# 08_FPGA.net
KiCad netlist of a schematic drawn in Altium Designer
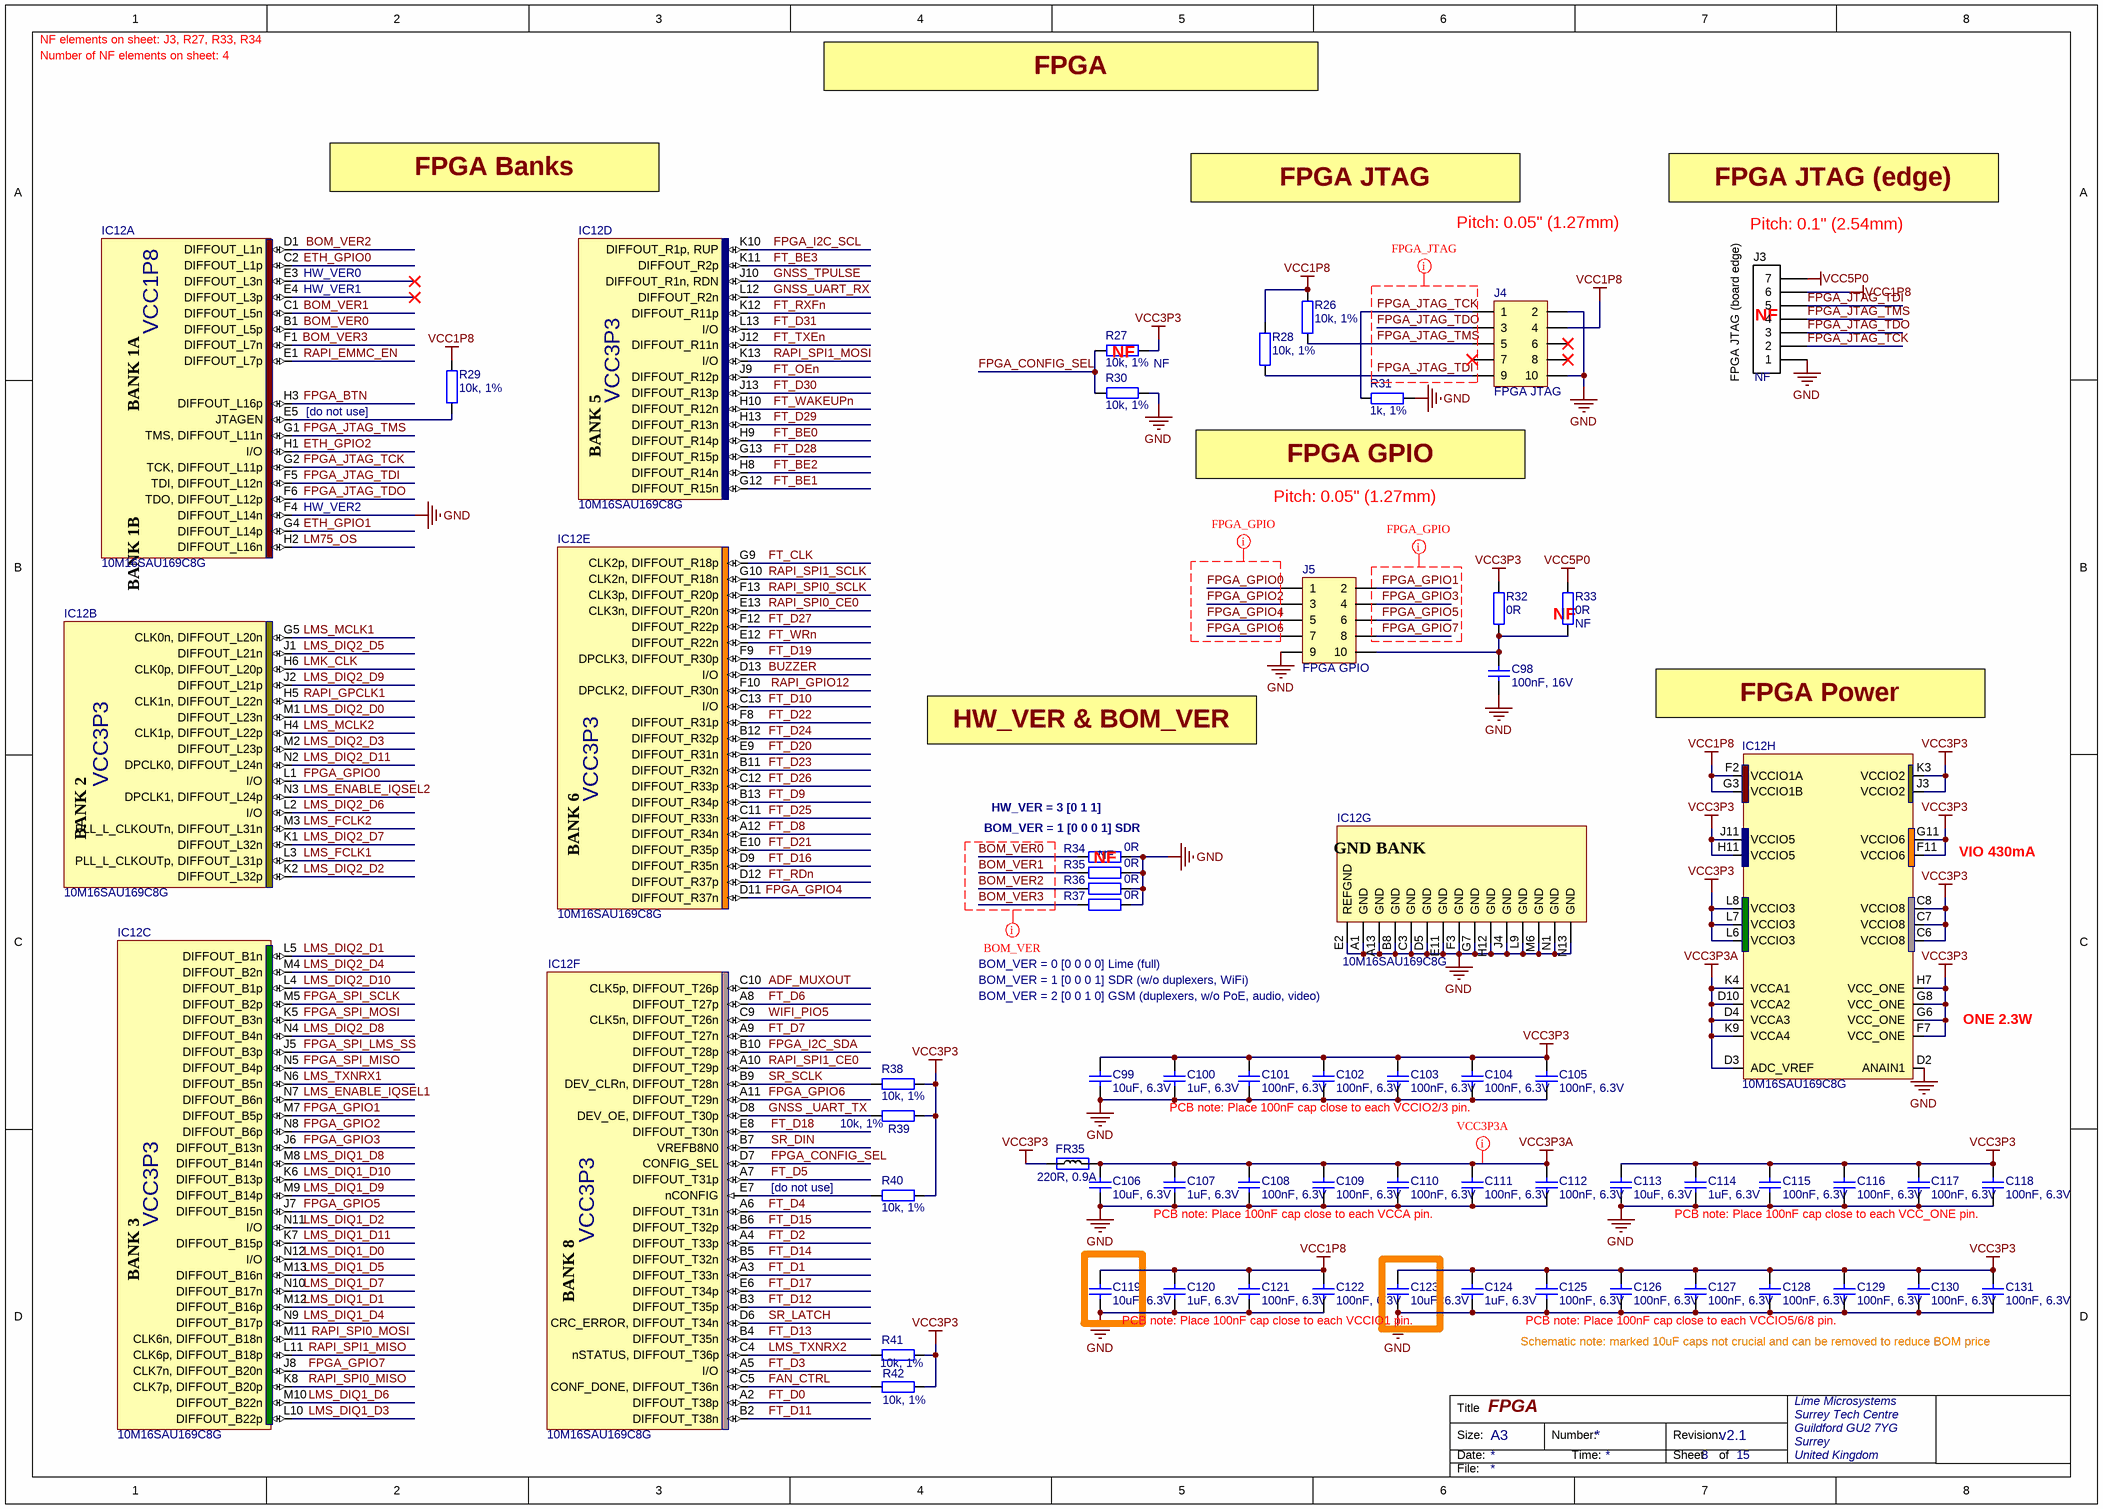
[diagram p0: 08_FPGA.SchDoc]

(export (version "E")
  (design (tool "Eeschema 10.0.6"))
  (components
    (comp (ref "C98")
      (value "100nF, 16V")
      (footprint "CAP0402")
      (fields
        (field (name "MANUFACTURER") "Murata Electronics")
        (field (name "TOLERANCE") "10 %")
        (field (name "MANUFACTURER PART NUMBER") "GRM155R71C104KA88D")
      )
      (libsource (lib "LimeMicroAltiumLib_schLib") (part "Cap_0402"))
    )
    (comp (ref "C99")
      (value "10uF, 6.3V")
      (footprint "CAP0603")
      (fields (field (name "TOLERANCE") "±20%") (field (name "MANUFACTURER") "Yageo"))
      (libsource (lib "LimeFPGAboard_schLib") (part "Cap_0603"))
    )
    (comp (ref "C100")
      (value "1uF, 6.3V")
      (footprint "CAP0201")
      (fields (field (name "TOLERANCE") "±20%") (field (name "MANUFACTURER") "TDK Corporation"))
      (libsource (lib "LimeMicroAltiumLib_schLib") (part "Cap_0402"))
    )
    (comp (ref "C101")
      (value "100nF, 6.3V")
      (footprint "CAP0201")
      (fields (field (name "MANUFACTURER") "Murata") (field (name "TOLERANCE") "10 %"))
      (libsource (lib "LimeMicroAltiumLib_schLib") (part "Cap_0402"))
    )
    (comp (ref "C102")
      (value "100nF, 6.3V")
      (footprint "CAP0201")
      (fields (field (name "MANUFACTURER") "Murata") (field (name "TOLERANCE") "10 %"))
      (libsource (lib "LimeMicroAltiumLib_schLib") (part "Cap_0402"))
    )
    (comp (ref "C103")
      (value "100nF, 6.3V")
      (footprint "CAP0201")
      (fields (field (name "MANUFACTURER") "Murata") (field (name "TOLERANCE") "10 %"))
      (libsource (lib "LimeMicroAltiumLib_schLib") (part "Cap_0402"))
    )
    (comp (ref "C104")
      (value "100nF, 6.3V")
      (footprint "CAP0201")
      (fields (field (name "MANUFACTURER") "Murata") (field (name "TOLERANCE") "10 %"))
      (libsource (lib "LimeMicroAltiumLib_schLib") (part "Cap_0402"))
    )
    (comp (ref "C105")
      (value "100nF, 6.3V")
      (footprint "CAP0201")
      (fields (field (name "MANUFACTURER") "Murata") (field (name "TOLERANCE") "10 %"))
      (libsource (lib "LimeMicroAltiumLib_schLib") (part "Cap_0402"))
    )
    (comp (ref "C106")
      (value "10uF, 6.3V")
      (footprint "CAP0603")
      (fields (field (name "TOLERANCE") "±20%") (field (name "MANUFACTURER") "Yageo"))
      (libsource (lib "LimeFPGAboard_schLib") (part "Cap_0603"))
    )
    (comp (ref "C107")
      (value "1uF, 6.3V")
      (footprint "CAP0201")
      (fields (field (name "TOLERANCE") "±20%") (field (name "MANUFACTURER") "TDK Corporation"))
      (libsource (lib "LimeMicroAltiumLib_schLib") (part "Cap_0402"))
    )
    (comp (ref "C108")
      (value "100nF, 6.3V")
      (footprint "CAP0201")
      (fields (field (name "MANUFACTURER") "Murata") (field (name "TOLERANCE") "10 %"))
      (libsource (lib "LimeMicroAltiumLib_schLib") (part "Cap_0402"))
    )
    (comp (ref "C109")
      (value "100nF, 6.3V")
      (footprint "CAP0201")
      (fields (field (name "MANUFACTURER") "Murata") (field (name "TOLERANCE") "10 %"))
      (libsource (lib "LimeMicroAltiumLib_schLib") (part "Cap_0402"))
    )
    (comp (ref "C110")
      (value "100nF, 6.3V")
      (footprint "CAP0201")
      (fields (field (name "MANUFACTURER") "Murata") (field (name "TOLERANCE") "10 %"))
      (libsource (lib "LimeMicroAltiumLib_schLib") (part "Cap_0402"))
    )
    (comp (ref "C111")
      (value "100nF, 6.3V")
      (footprint "CAP0201")
      (fields (field (name "MANUFACTURER") "Murata") (field (name "TOLERANCE") "10 %"))
      (libsource (lib "LimeMicroAltiumLib_schLib") (part "Cap_0402"))
    )
    (comp (ref "C112")
      (value "100nF, 6.3V")
      (footprint "CAP0201")
      (fields (field (name "MANUFACTURER") "Murata") (field (name "TOLERANCE") "10 %"))
      (libsource (lib "LimeMicroAltiumLib_schLib") (part "Cap_0402"))
    )
    (comp (ref "C113")
      (value "10uF, 6.3V")
      (footprint "CAP0603")
      (fields (field (name "TOLERANCE") "±20%") (field (name "MANUFACTURER") "Yageo"))
      (libsource (lib "LimeFPGAboard_schLib") (part "Cap_0603"))
    )
    (comp (ref "C114")
      (value "1uF, 6.3V")
      (footprint "CAP0201")
      (fields (field (name "TOLERANCE") "±20%") (field (name "MANUFACTURER") "TDK Corporation"))
      (libsource (lib "LimeMicroAltiumLib_schLib") (part "Cap_0402"))
    )
    (comp (ref "C115")
      (value "100nF, 6.3V")
      (footprint "CAP0201")
      (fields (field (name "MANUFACTURER") "Murata") (field (name "TOLERANCE") "10 %"))
      (libsource (lib "LimeMicroAltiumLib_schLib") (part "Cap_0402"))
    )
    (comp (ref "C116")
      (value "100nF, 6.3V")
      (footprint "CAP0201")
      (fields (field (name "MANUFACTURER") "Murata") (field (name "TOLERANCE") "10 %"))
      (libsource (lib "LimeMicroAltiumLib_schLib") (part "Cap_0402"))
    )
    (comp (ref "C117")
      (value "100nF, 6.3V")
      (footprint "CAP0201")
      (fields (field (name "MANUFACTURER") "Murata") (field (name "TOLERANCE") "10 %"))
      (libsource (lib "LimeMicroAltiumLib_schLib") (part "Cap_0402"))
    )
    (comp (ref "C118")
      (value "100nF, 6.3V")
      (footprint "CAP0201")
      (fields (field (name "MANUFACTURER") "Murata") (field (name "TOLERANCE") "10 %"))
      (libsource (lib "LimeMicroAltiumLib_schLib") (part "Cap_0402"))
    )
    (comp (ref "C119")
      (value "10uF, 6.3V")
      (footprint "CAP0603")
      (fields (field (name "TOLERANCE") "±20%") (field (name "MANUFACTURER") "Yageo"))
      (libsource (lib "LimeFPGAboard_schLib") (part "Cap_0603"))
    )
    (comp (ref "C120")
      (value "1uF, 6.3V")
      (footprint "CAP0201")
      (fields (field (name "TOLERANCE") "±20%") (field (name "MANUFACTURER") "TDK Corporation"))
      (libsource (lib "LimeMicroAltiumLib_schLib") (part "Cap_0402"))
    )
    (comp (ref "C121")
      (value "100nF, 6.3V")
      (footprint "CAP0201")
      (fields (field (name "MANUFACTURER") "Murata") (field (name "TOLERANCE") "10 %"))
      (libsource (lib "LimeMicroAltiumLib_schLib") (part "Cap_0402"))
    )
    (comp (ref "C122")
      (value "100nF, 6.3V")
      (footprint "CAP0201")
      (fields (field (name "MANUFACTURER") "Murata") (field (name "TOLERANCE") "10 %"))
      (libsource (lib "LimeMicroAltiumLib_schLib") (part "Cap_0402"))
    )
    (comp (ref "C123")
      (value "10uF, 6.3V")
      (footprint "CAP0603")
      (fields (field (name "TOLERANCE") "±20%") (field (name "MANUFACTURER") "Yageo"))
      (libsource (lib "LimeFPGAboard_schLib") (part "Cap_0603"))
    )
    (comp (ref "C124")
      (value "1uF, 6.3V")
      (footprint "CAP0201")
      (fields (field (name "TOLERANCE") "±20%") (field (name "MANUFACTURER") "TDK Corporation"))
      (libsource (lib "LimeMicroAltiumLib_schLib") (part "Cap_0402"))
    )
    (comp (ref "C125")
      (value "100nF, 6.3V")
      (footprint "CAP0201")
      (fields (field (name "MANUFACTURER") "Murata") (field (name "TOLERANCE") "10 %"))
      (libsource (lib "LimeMicroAltiumLib_schLib") (part "Cap_0402"))
    )
    (comp (ref "C126")
      (value "100nF, 6.3V")
      (footprint "CAP0201")
      (fields (field (name "MANUFACTURER") "Murata") (field (name "TOLERANCE") "10 %"))
      (libsource (lib "LimeMicroAltiumLib_schLib") (part "Cap_0402"))
    )
    (comp (ref "C127")
      (value "100nF, 6.3V")
      (footprint "CAP0201")
      (fields (field (name "MANUFACTURER") "Murata") (field (name "TOLERANCE") "10 %"))
      (libsource (lib "LimeMicroAltiumLib_schLib") (part "Cap_0402"))
    )
    (comp (ref "C128")
      (value "100nF, 6.3V")
      (footprint "CAP0201")
      (fields (field (name "MANUFACTURER") "Murata") (field (name "TOLERANCE") "10 %"))
      (libsource (lib "LimeMicroAltiumLib_schLib") (part "Cap_0402"))
    )
    (comp (ref "C129")
      (value "100nF, 6.3V")
      (footprint "CAP0201")
      (fields (field (name "MANUFACTURER") "Murata") (field (name "TOLERANCE") "10 %"))
      (libsource (lib "LimeMicroAltiumLib_schLib") (part "Cap_0402"))
    )
    (comp (ref "C130")
      (value "100nF, 6.3V")
      (footprint "CAP0201")
      (fields (field (name "MANUFACTURER") "Murata") (field (name "TOLERANCE") "10 %"))
      (libsource (lib "LimeMicroAltiumLib_schLib") (part "Cap_0402"))
    )
    (comp (ref "C131")
      (value "100nF, 6.3V")
      (footprint "CAP0201")
      (fields (field (name "MANUFACTURER") "Murata") (field (name "TOLERANCE") "10 %"))
      (libsource (lib "LimeMicroAltiumLib_schLib") (part "Cap_0402"))
    )
    (comp (ref "FR35")
      (value "220R, 0.9A")
      (footprint "RES0402")
      (fields (field (name "MANUFACTURER") "TDK Corporation"))
      (libsource (lib "LimeFPGAboard_schLib") (part "Ferrite"))
    )
    (comp (ref "IC12")
      (value "10M16SAU169C8G")
      (footprint "10M16SAU169C8G")
      (fields (field (name "MANUFACTURER") "Altera"))
      (libsource (lib "LimeMicroAltiumLib_schLib") (part "10M16SAU169C8G"))
    )
    (comp (ref "J3")
      (value "FPGA JTAG (board edge)")
      (footprint "Header7x1_TH")
      (description "Header, 7-pin")
      (fields (field (name "MANUFACTURER") "Sullins Connector Solutions") (field (name "ASSEMBLY INFO") "NF"))
      (libsource (lib "LimeMicroAltiumLib_schLib") (part "Header7P"))
    )
    (comp (ref "J4")
      (value "FPGA JTAG")
      (footprint "SWD_10_pin")
      (description "Header, 5-Pin, Dual row")
      (fields (field (name "MANUFACTURER") "Harwin Inc"))
      (libsource (lib "LimeMicroAltiumLib_schLib") (part "Header 5X2_SWD"))
    )
    (comp (ref "J5")
      (value "FPGA GPIO")
      (footprint "SWD_10_pin")
      (description "Header, 5-Pin, Dual row")
      (fields (field (name "MANUFACTURER") "Harwin Inc"))
      (libsource (lib "LimeMicroAltiumLib_schLib") (part "Header 5X2_SWD"))
    )
    (comp (ref "R26")
      (value "10k, 1%")
      (footprint "RES0402")
      (fields (field (name "MANUFACTURER") "Yageo") (field (name "TOLERANCE") "±1%"))
      (libsource (lib "LimeMicroAltiumLib_schLib") (part "Res_0402"))
    )
    (comp (ref "R27")
      (value "10k, 1%")
      (footprint "RES0402")
      (fields
        (field (name "ASSEMBLY INFO") "NF")
        (field (name "MANUFACTURER") "Yageo")
        (field (name "TOLERANCE") "±1%")
      )
      (libsource (lib "LimeMicroAltiumLib_schLib") (part "Res_0402"))
    )
    (comp (ref "R28")
      (value "10k, 1%")
      (footprint "RES0402")
      (fields (field (name "MANUFACTURER") "Yageo") (field (name "TOLERANCE") "±1%"))
      (libsource (lib "LimeMicroAltiumLib_schLib") (part "Res_0402"))
    )
    (comp (ref "R29")
      (value "10k, 1%")
      (footprint "RES0402")
      (fields (field (name "MANUFACTURER") "Yageo") (field (name "TOLERANCE") "±1%"))
      (libsource (lib "LimeMicroAltiumLib_schLib") (part "Res_0402"))
    )
    (comp (ref "R30")
      (value "10k, 1%")
      (footprint "RES0402")
      (fields (field (name "MANUFACTURER") "Yageo") (field (name "TOLERANCE") "±1%"))
      (libsource (lib "LimeMicroAltiumLib_schLib") (part "Res_0402"))
    )
    (comp (ref "R31")
      (value "1k, 1%")
      (footprint "RES0402")
      (fields (field (name "MANUFACTURER") "Stackpole Electronics Inc") (field (name "TOLERANCE") "±1%"))
      (libsource (lib "LimeMicroAltiumLib_schLib") (part "Res_0402"))
    )
    (comp (ref "R32")
      (value "0R")
      (footprint "RES0402")
      (fields (field (name "MANUFACTURER") "Yageo") (field (name "TOLERANCE") "Jumper"))
      (libsource (lib "LimeFPGAboard_schLib") (part "Res_0402"))
    )
    (comp (ref "R33")
      (value "0R")
      (footprint "RES0402")
      (fields
        (field (name "MANUFACTURER") "Yageo")
        (field (name "ASSEMBLY INFO") "NF")
        (field (name "TOLERANCE") "Jumper")
      )
      (libsource (lib "LimeFPGAboard_schLib") (part "Res_0402"))
    )
    (comp (ref "R34")
      (value "0R")
      (footprint "RES0402")
      (fields
        (field (name "MANUFACTURER") "Yageo")
        (field (name "ASSEMBLY INFO") "NF")
        (field (name "TOLERANCE") "Jumper")
      )
      (libsource (lib "LimeFPGAboard_schLib") (part "Res_0402"))
    )
    (comp (ref "R35")
      (value "0R")
      (footprint "RES0402")
      (fields (field (name "MANUFACTURER") "Yageo") (field (name "TOLERANCE") "Jumper"))
      (libsource (lib "LimeFPGAboard_schLib") (part "Res_0402"))
    )
    (comp (ref "R36")
      (value "0R")
      (footprint "RES0402")
      (fields (field (name "MANUFACTURER") "Yageo") (field (name "TOLERANCE") "Jumper"))
      (libsource (lib "LimeFPGAboard_schLib") (part "Res_0402"))
    )
    (comp (ref "R37")
      (value "0R")
      (footprint "RES0402")
      (fields (field (name "MANUFACTURER") "Yageo") (field (name "TOLERANCE") "Jumper"))
      (libsource (lib "LimeFPGAboard_schLib") (part "Res_0402"))
    )
    (comp (ref "R38")
      (value "10k, 1%")
      (footprint "RES0402")
      (fields (field (name "MANUFACTURER") "Yageo") (field (name "TOLERANCE") "±1%"))
      (libsource (lib "LimeMicroAltiumLib_schLib") (part "Res_0402"))
    )
    (comp (ref "R39")
      (value "10k, 1%")
      (footprint "RES0402")
      (fields (field (name "MANUFACTURER") "Yageo") (field (name "TOLERANCE") "±1%"))
      (libsource (lib "LimeMicroAltiumLib_schLib") (part "Res_0402"))
    )
    (comp (ref "R40")
      (value "10k, 1%")
      (footprint "RES0402")
      (fields (field (name "MANUFACTURER") "Yageo") (field (name "TOLERANCE") "±1%"))
      (libsource (lib "LimeMicroAltiumLib_schLib") (part "Res_0402"))
    )
    (comp (ref "R41")
      (value "10k, 1%")
      (footprint "RES0402")
      (fields (field (name "MANUFACTURER") "Yageo") (field (name "TOLERANCE") "±1%"))
      (libsource (lib "LimeMicroAltiumLib_schLib") (part "Res_0402"))
    )
    (comp (ref "R42")
      (value "10k, 1%")
      (footprint "RES0402")
      (fields (field (name "MANUFACTURER") "Yageo") (field (name "TOLERANCE") "±1%"))
      (libsource (lib "LimeMicroAltiumLib_schLib") (part "Res_0402"))
    )
  )
  (nets
    (net (code "1") (name "/ADF_MUXOUT") (class "Default")
      (node (ref "IC12") (pin "C10") (pinfunction "CLK5p,_DIFFOUT_T26p_C10") (pintype "bidirectional"))
    )
    (net (code "2") (name "/BOM_VER0") (class "Default")
      (node (ref "IC12") (pin "B1") (pinfunction "DIFFOUT_L5p_B1") (pintype "bidirectional"))
      (node (ref "R34") (pin "2") (pinfunction "2_2") (pintype "passive"))
    )
    (net (code "3") (name "/BOM_VER1") (class "Default")
      (node (ref "IC12") (pin "C1") (pinfunction "DIFFOUT_L5n_C1") (pintype "bidirectional"))
      (node (ref "R35") (pin "2") (pinfunction "2_2") (pintype "passive"))
    )
    (net (code "4") (name "/BOM_VER2") (class "Default")
      (node (ref "IC12") (pin "D1") (pinfunction "DIFFOUT_L1n_D1") (pintype "bidirectional"))
      (node (ref "R36") (pin "2") (pinfunction "2_2") (pintype "passive"))
    )
    (net (code "5") (name "/BOM_VER3") (class "Default")
      (node (ref "IC12") (pin "F1") (pinfunction "DIFFOUT_L7n_F1") (pintype "bidirectional"))
      (node (ref "R37") (pin "2") (pinfunction "2_2") (pintype "passive"))
    )
    (net (code "6") (name "/BUZZER") (class "Default")
      (node (ref "IC12") (pin "D13") (pinfunction "I/O_D13") (pintype "bidirectional"))
    )
    (net (code "7") (name "/ETH_GPIO0") (class "Default")
      (node (ref "IC12") (pin "C2") (pinfunction "DIFFOUT_L1p_C2") (pintype "bidirectional"))
    )
    (net (code "8") (name "/ETH_GPIO1") (class "Default")
      (node (ref "IC12") (pin "G4") (pinfunction "DIFFOUT_L14p_G4") (pintype "bidirectional"))
    )
    (net (code "9") (name "/ETH_GPIO2") (class "Default")
      (node (ref "IC12") (pin "H1") (pinfunction "I/O_H1") (pintype "bidirectional"))
    )
    (net (code "10") (name "/FAN_CTRL") (class "Default")
      (node (ref "IC12") (pin "C5") (pinfunction "CONF_DONE,_DIFFOUT_T36n_C5") (pintype "bidirectional"))
      (node (ref "R42") (pin "2") (pinfunction "2_2") (pintype "passive"))
    )
    (net (code "11") (name "/FPGA_BTN") (class "Default")
      (node (ref "IC12") (pin "H3") (pinfunction "DIFFOUT_L16p_H3") (pintype "bidirectional"))
    )
    (net (code "12") (name "/FPGA_CONFIG_SEL") (class "Default")
      (node (ref "IC12") (pin "D7") (pinfunction "CONFIG_SEL_D7") (pintype "bidirectional"))
      (node (ref "R27") (pin "2") (pinfunction "2_2") (pintype "passive"))
      (node (ref "R30") (pin "2") (pinfunction "2_2") (pintype "passive"))
    )
    (net (code "13") (name "/FPGA_GPIO0") (class "Default")
      (node (ref "IC12") (pin "L1") (pinfunction "I/O_L1") (pintype "bidirectional"))
      (node (ref "J5") (pin "1") (pinfunction "1_1") (pintype "passive"))
    )
    (net (code "14") (name "/FPGA_GPIO1") (class "Default")
      (node (ref "IC12") (pin "M7") (pinfunction "DIFFOUT_B5p_M7") (pintype "bidirectional"))
      (node (ref "J5") (pin "2") (pinfunction "2_2") (pintype "passive"))
    )
    (net (code "15") (name "/FPGA_GPIO2") (class "Default")
      (node (ref "IC12") (pin "N8") (pinfunction "DIFFOUT_B6p_N8") (pintype "bidirectional"))
      (node (ref "J5") (pin "3") (pinfunction "3_3") (pintype "passive"))
    )
    (net (code "16") (name "/FPGA_GPIO3") (class "Default")
      (node (ref "IC12") (pin "J6") (pinfunction "DIFFOUT_B13n_J6") (pintype "bidirectional"))
      (node (ref "J5") (pin "4") (pinfunction "4_4") (pintype "passive"))
    )
    (net (code "17") (name "/FPGA_GPIO4") (class "Default")
      (node (ref "IC12") (pin "D11") (pinfunction "DIFFOUT_R37n_D11") (pintype "bidirectional"))
      (node (ref "J5") (pin "5") (pinfunction "5_5") (pintype "passive"))
    )
    (net (code "18") (name "/FPGA_GPIO5") (class "Default")
      (node (ref "IC12") (pin "J7") (pinfunction "DIFFOUT_B15n_J7") (pintype "bidirectional"))
      (node (ref "J5") (pin "6") (pinfunction "6_6") (pintype "passive"))
    )
    (net (code "19") (name "/FPGA_GPIO6") (class "Default")
      (node (ref "IC12") (pin "A11") (pinfunction "DIFFOUT_T29n_A11") (pintype "bidirectional"))
      (node (ref "J5") (pin "7") (pinfunction "7_7") (pintype "passive"))
    )
    (net (code "20") (name "/FPGA_GPIO7") (class "Default")
      (node (ref "IC12") (pin "J8") (pinfunction "CLK7n,_DIFFOUT_B20n_J8") (pintype "bidirectional"))
      (node (ref "J5") (pin "8") (pinfunction "8_8") (pintype "passive"))
    )
    (net (code "21") (name "/FPGA_I2C_SCL") (class "Default")
      (node (ref "IC12") (pin "K10") (pinfunction "DIFFOUT_R1p,_RUP_K10") (pintype "bidirectional"))
    )
    (net (code "22") (name "/FPGA_I2C_SDA") (class "Default")
      (node (ref "IC12") (pin "B10") (pinfunction "DIFFOUT_T28p_B10") (pintype "bidirectional"))
    )
    (net (code "23") (name "/FPGA_JTAG_TCK") (class "Default")
      (node (ref "IC12") (pin "G2") (pinfunction "TCK,_DIFFOUT_L11p_G2") (pintype "bidirectional"))
      (node (ref "J3") (pin "2") (pinfunction "2_2") (pintype "passive"))
      (node (ref "J4") (pin "1") (pinfunction "1_1") (pintype "passive"))
      (node (ref "R31") (pin "1") (pinfunction "1_1") (pintype "passive"))
    )
    (net (code "24") (name "/FPGA_JTAG_TDI") (class "Default")
      (node (ref "IC12") (pin "F5") (pinfunction "TDI,_DIFFOUT_L12n_F5") (pintype "bidirectional"))
      (node (ref "J3") (pin "5") (pinfunction "5_5") (pintype "passive"))
      (node (ref "J4") (pin "9") (pinfunction "9_9") (pintype "passive"))
      (node (ref "R28") (pin "1") (pinfunction "1_1") (pintype "passive"))
    )
    (net (code "25") (name "/FPGA_JTAG_TDO") (class "Default")
      (node (ref "IC12") (pin "F6") (pinfunction "TDO,_DIFFOUT_L12p_F6") (pintype "bidirectional"))
      (node (ref "J3") (pin "3") (pinfunction "3_3") (pintype "passive"))
      (node (ref "J4") (pin "3") (pinfunction "3_3") (pintype "passive"))
    )
    (net (code "26") (name "/FPGA_JTAG_TMS") (class "Default")
      (node (ref "IC12") (pin "G1") (pinfunction "TMS,_DIFFOUT_L11n_G1") (pintype "bidirectional"))
      (node (ref "J3") (pin "4") (pinfunction "4_4") (pintype "passive"))
      (node (ref "J4") (pin "5") (pinfunction "5_5") (pintype "passive"))
      (node (ref "R26") (pin "1") (pinfunction "1_1") (pintype "passive"))
    )
    (net (code "27") (name "/FPGA_SPI_LMS_SS") (class "Default")
      (node (ref "IC12") (pin "J5") (pinfunction "DIFFOUT_B3p_J5") (pintype "bidirectional"))
    )
    (net (code "28") (name "/FPGA_SPI_MISO") (class "Default")
      (node (ref "IC12") (pin "N5") (pinfunction "DIFFOUT_B4p_N5") (pintype "bidirectional"))
    )
    (net (code "29") (name "/FPGA_SPI_MOSI") (class "Default")
      (node (ref "IC12") (pin "K5") (pinfunction "DIFFOUT_B3n_K5") (pintype "bidirectional"))
    )
    (net (code "30") (name "/FPGA_SPI_SCLK") (class "Default")
      (node (ref "IC12") (pin "M5") (pinfunction "DIFFOUT_B2p_M5") (pintype "bidirectional"))
    )
    (net (code "31") (name "/FT_BE0") (class "Default")
      (node (ref "IC12") (pin "H9") (pinfunction "DIFFOUT_R14p_H9") (pintype "bidirectional"))
    )
    (net (code "32") (name "/FT_BE1") (class "Default")
      (node (ref "IC12") (pin "G12") (pinfunction "DIFFOUT_R15n_G12") (pintype "bidirectional"))
    )
    (net (code "33") (name "/FT_BE2") (class "Default")
      (node (ref "IC12") (pin "H8") (pinfunction "DIFFOUT_R14n_H8") (pintype "bidirectional"))
    )
    (net (code "34") (name "/FT_BE3") (class "Default")
      (node (ref "IC12") (pin "K11") (pinfunction "DIFFOUT_R2p_K11") (pintype "bidirectional"))
    )
    (net (code "35") (name "/FT_CLK") (class "Default")
      (node (ref "IC12") (pin "G9") (pinfunction "CLK2p,_DIFFOUT_R18p_G9") (pintype "bidirectional"))
    )
    (net (code "36") (name "/FT_D0") (class "Default")
      (node (ref "IC12") (pin "A2") (pinfunction "DIFFOUT_T38p_A2") (pintype "bidirectional"))
    )
    (net (code "37") (name "/FT_D1") (class "Default")
      (node (ref "IC12") (pin "A3") (pinfunction "DIFFOUT_T33n_A3") (pintype "bidirectional"))
    )
    (net (code "38") (name "/FT_D2") (class "Default")
      (node (ref "IC12") (pin "A4") (pinfunction "DIFFOUT_T33p_A4") (pintype "bidirectional"))
    )
    (net (code "39") (name "/FT_D3") (class "Default")
      (node (ref "IC12") (pin "A5") (pinfunction "I/O_A5") (pintype "bidirectional"))
    )
    (net (code "40") (name "/FT_D4") (class "Default")
      (node (ref "IC12") (pin "A6") (pinfunction "DIFFOUT_T31n_A6") (pintype "bidirectional"))
    )
    (net (code "41") (name "/FT_D5") (class "Default")
      (node (ref "IC12") (pin "A7") (pinfunction "DIFFOUT_T31p_A7") (pintype "bidirectional"))
    )
    (net (code "42") (name "/FT_D6") (class "Default")
      (node (ref "IC12") (pin "A8") (pinfunction "DIFFOUT_T27p_A8") (pintype "bidirectional"))
    )
    (net (code "43") (name "/FT_D7") (class "Default")
      (node (ref "IC12") (pin "A9") (pinfunction "DIFFOUT_T27n_A9") (pintype "bidirectional"))
    )
    (net (code "44") (name "/FT_D8") (class "Default")
      (node (ref "IC12") (pin "A12") (pinfunction "DIFFOUT_R34n_A12") (pintype "bidirectional"))
    )
    (net (code "45") (name "/FT_D9") (class "Default")
      (node (ref "IC12") (pin "B13") (pinfunction "DIFFOUT_R34p_B13") (pintype "bidirectional"))
    )
    (net (code "46") (name "/FT_D10") (class "Default")
      (node (ref "IC12") (pin "C13") (pinfunction "I/O_C13") (pintype "bidirectional"))
    )
    (net (code "47") (name "/FT_D11") (class "Default")
      (node (ref "IC12") (pin "B2") (pinfunction "DIFFOUT_T38n_B2") (pintype "bidirectional"))
    )
    (net (code "48") (name "/FT_D12") (class "Default")
      (node (ref "IC12") (pin "B3") (pinfunction "DIFFOUT_T35p_B3") (pintype "bidirectional"))
    )
    (net (code "49") (name "/FT_D13") (class "Default")
      (node (ref "IC12") (pin "B4") (pinfunction "DIFFOUT_T35n_B4") (pintype "bidirectional"))
    )
    (net (code "50") (name "/FT_D14") (class "Default")
      (node (ref "IC12") (pin "B5") (pinfunction "DIFFOUT_T32n_B5") (pintype "bidirectional"))
    )
    (net (code "51") (name "/FT_D15") (class "Default")
      (node (ref "IC12") (pin "B6") (pinfunction "DIFFOUT_T32p_B6") (pintype "bidirectional"))
    )
    (net (code "52") (name "/FT_D16") (class "Default")
      (node (ref "IC12") (pin "D9") (pinfunction "DIFFOUT_R35n_D9") (pintype "bidirectional"))
    )
    (net (code "53") (name "/FT_D17") (class "Default")
      (node (ref "IC12") (pin "E6") (pinfunction "DIFFOUT_T34p_E6") (pintype "bidirectional"))
    )
    (net (code "54") (name "/FT_D18") (class "Default")
      (node (ref "IC12") (pin "E8") (pinfunction "DIFFOUT_T30n_E8") (pintype "bidirectional"))
    )
    (net (code "55") (name "/FT_D19") (class "Default")
      (node (ref "IC12") (pin "F9") (pinfunction "DPCLK3,_DIFFOUT_R30p_F9") (pintype "bidirectional"))
    )
    (net (code "56") (name "/FT_D20") (class "Default")
      (node (ref "IC12") (pin "E9") (pinfunction "DIFFOUT_R31n_E9") (pintype "bidirectional"))
    )
    (net (code "57") (name "/FT_D21") (class "Default")
      (node (ref "IC12") (pin "E10") (pinfunction "DIFFOUT_R35p_E10") (pintype "bidirectional"))
    )
    (net (code "58") (name "/FT_D22") (class "Default")
      (node (ref "IC12") (pin "F8") (pinfunction "DIFFOUT_R31p_F8") (pintype "bidirectional"))
    )
    (net (code "59") (name "/FT_D23") (class "Default")
      (node (ref "IC12") (pin "B11") (pinfunction "DIFFOUT_R32n_B11") (pintype "bidirectional"))
    )
    (net (code "60") (name "/FT_D24") (class "Default")
      (node (ref "IC12") (pin "B12") (pinfunction "DIFFOUT_R32p_B12") (pintype "bidirectional"))
    )
    (net (code "61") (name "/FT_D25") (class "Default")
      (node (ref "IC12") (pin "C11") (pinfunction "DIFFOUT_R33n_C11") (pintype "bidirectional"))
    )
    (net (code "62") (name "/FT_D26") (class "Default")
      (node (ref "IC12") (pin "C12") (pinfunction "DIFFOUT_R33p_C12") (pintype "bidirectional"))
    )
    (net (code "63") (name "/FT_D27") (class "Default")
      (node (ref "IC12") (pin "F12") (pinfunction "DIFFOUT_R22p_F12") (pintype "bidirectional"))
    )
    (net (code "64") (name "/FT_D28") (class "Default")
      (node (ref "IC12") (pin "G13") (pinfunction "DIFFOUT_R15p_G13") (pintype "bidirectional"))
    )
    (net (code "65") (name "/FT_D29") (class "Default")
      (node (ref "IC12") (pin "H13") (pinfunction "DIFFOUT_R13n_H13") (pintype "bidirectional"))
    )
    (net (code "66") (name "/FT_D30") (class "Default")
      (node (ref "IC12") (pin "J13") (pinfunction "DIFFOUT_R13p_J13") (pintype "bidirectional"))
    )
    (net (code "67") (name "/FT_D31") (class "Default")
      (node (ref "IC12") (pin "L13") (pinfunction "I/O_L13") (pintype "bidirectional"))
    )
    (net (code "68") (name "/FT_OEn") (class "Default")
      (node (ref "IC12") (pin "J9") (pinfunction "DIFFOUT_R12p_J9") (pintype "bidirectional"))
    )
    (net (code "69") (name "/FT_RDn") (class "Default")
      (node (ref "IC12") (pin "D12") (pinfunction "DIFFOUT_R37p_D12") (pintype "bidirectional"))
    )
    (net (code "70") (name "/FT_RXFn") (class "Default")
      (node (ref "IC12") (pin "K12") (pinfunction "DIFFOUT_R11p_K12") (pintype "bidirectional"))
    )
    (net (code "71") (name "/FT_TXEn") (class "Default")
      (node (ref "IC12") (pin "J12") (pinfunction "DIFFOUT_R11n_J12") (pintype "bidirectional"))
    )
    (net (code "72") (name "/FT_WAKEUPn") (class "Default")
      (node (ref "IC12") (pin "H10") (pinfunction "DIFFOUT_R12n_H10") (pintype "bidirectional"))
    )
    (net (code "73") (name "/FT_WRn") (class "Default")
      (node (ref "IC12") (pin "E12") (pinfunction "DIFFOUT_R22n_E12") (pintype "bidirectional"))
    )
    (net (code "74") (name "/GNSS _UART_TX") (class "Default")
      (node (ref "IC12") (pin "D8") (pinfunction "DEV_OE,_DIFFOUT_T30p_D8") (pintype "bidirectional"))
      (node (ref "R39") (pin "2") (pinfunction "2_2") (pintype "passive"))
    )
    (net (code "75") (name "/GNSS_TPULSE") (class "Default")
      (node (ref "IC12") (pin "J10") (pinfunction "DIFFOUT_R1n,_RDN_J10") (pintype "bidirectional"))
    )
    (net (code "76") (name "/GNSS_UART_RX") (class "Default")
      (node (ref "IC12") (pin "L12") (pinfunction "DIFFOUT_R2n_L12") (pintype "bidirectional"))
    )
    (net (code "77") (name "/LM75_OS") (class "Default")
      (node (ref "IC12") (pin "H2") (pinfunction "DIFFOUT_L16n_H2") (pintype "bidirectional"))
    )
    (net (code "78") (name "/LMK_CLK") (class "Default")
      (node (ref "IC12") (pin "H6") (pinfunction "CLK0p,_DIFFOUT_L20p_H6") (pintype "bidirectional"))
    )
    (net (code "79") (name "/LMS_DIQ1_D0") (class "Default")
      (node (ref "IC12") (pin "N12") (pinfunction "I/O_N12") (pintype "bidirectional"))
    )
    (net (code "80") (name "/LMS_DIQ1_D1") (class "Default")
      (node (ref "IC12") (pin "M12") (pinfunction "DIFFOUT_B16p_M12") (pintype "bidirectional"))
    )
    (net (code "81") (name "/LMS_DIQ1_D2") (class "Default")
      (node (ref "IC12") (pin "N11") (pinfunction "I/O_N11") (pintype "bidirectional"))
    )
    (net (code "82") (name "/LMS_DIQ1_D3") (class "Default")
      (node (ref "IC12") (pin "L10") (pinfunction "DIFFOUT_B22p_L10") (pintype "bidirectional"))
    )
    (net (code "83") (name "/LMS_DIQ1_D4") (class "Default")
      (node (ref "IC12") (pin "N9") (pinfunction "DIFFOUT_B17p_N9") (pintype "bidirectional"))
    )
    (net (code "84") (name "/LMS_DIQ1_D5") (class "Default")
      (node (ref "IC12") (pin "M13") (pinfunction "DIFFOUT_B16n_M13") (pintype "bidirectional"))
    )
    (net (code "85") (name "/LMS_DIQ1_D6") (class "Default")
      (node (ref "IC12") (pin "M10") (pinfunction "DIFFOUT_B22n_M10") (pintype "bidirectional"))
    )
    (net (code "86") (name "/LMS_DIQ1_D7") (class "Default")
      (node (ref "IC12") (pin "N10") (pinfunction "DIFFOUT_B17n_N10") (pintype "bidirectional"))
    )
    (net (code "87") (name "/LMS_DIQ1_D8") (class "Default")
      (node (ref "IC12") (pin "M8") (pinfunction "DIFFOUT_B14n_M8") (pintype "bidirectional"))
    )
    (net (code "88") (name "/LMS_DIQ1_D9") (class "Default")
      (node (ref "IC12") (pin "M9") (pinfunction "DIFFOUT_B14p_M9") (pintype "bidirectional"))
    )
    (net (code "89") (name "/LMS_DIQ1_D10") (class "Default")
      (node (ref "IC12") (pin "K6") (pinfunction "DIFFOUT_B13p_K6") (pintype "bidirectional"))
    )
    (net (code "90") (name "/LMS_DIQ1_D11") (class "Default")
      (node (ref "IC12") (pin "K7") (pinfunction "DIFFOUT_B15p_K7") (pintype "bidirectional"))
    )
    (net (code "91") (name "/LMS_DIQ2_D0") (class "Default")
      (node (ref "IC12") (pin "M1") (pinfunction "DIFFOUT_L23n_M1") (pintype "bidirectional"))
    )
    (net (code "92") (name "/LMS_DIQ2_D1") (class "Default")
      (node (ref "IC12") (pin "L5") (pinfunction "DIFFOUT_B1n_L5") (pintype "bidirectional"))
    )
    (net (code "93") (name "/LMS_DIQ2_D2") (class "Default")
      (node (ref "IC12") (pin "K2") (pinfunction "DIFFOUT_L32p_K2") (pintype "bidirectional"))
    )
    (net (code "94") (name "/LMS_DIQ2_D3") (class "Default")
      (node (ref "IC12") (pin "M2") (pinfunction "DIFFOUT_L23p_M2") (pintype "bidirectional"))
    )
    (net (code "95") (name "/LMS_DIQ2_D4") (class "Default")
      (node (ref "IC12") (pin "M4") (pinfunction "DIFFOUT_B2n_M4") (pintype "bidirectional"))
    )
    (net (code "96") (name "/LMS_DIQ2_D5") (class "Default")
      (node (ref "IC12") (pin "J1") (pinfunction "DIFFOUT_L21n_J1") (pintype "bidirectional"))
    )
    (net (code "97") (name "/LMS_DIQ2_D6") (class "Default")
      (node (ref "IC12") (pin "L2") (pinfunction "I/O_L2") (pintype "bidirectional"))
    )
    (net (code "98") (name "/LMS_DIQ2_D7") (class "Default")
      (node (ref "IC12") (pin "K1") (pinfunction "DIFFOUT_L32n_K1") (pintype "bidirectional"))
    )
    (net (code "99") (name "/LMS_DIQ2_D8") (class "Default")
      (node (ref "IC12") (pin "N4") (pinfunction "DIFFOUT_B4n_N4") (pintype "bidirectional"))
    )
    (net (code "100") (name "/LMS_DIQ2_D9") (class "Default")
      (node (ref "IC12") (pin "J2") (pinfunction "DIFFOUT_L21p_J2") (pintype "bidirectional"))
    )
    (net (code "101") (name "/LMS_DIQ2_D10") (class "Default")
      (node (ref "IC12") (pin "L4") (pinfunction "DIFFOUT_B1p_L4") (pintype "bidirectional"))
    )
    (net (code "102") (name "/LMS_DIQ2_D11") (class "Default")
      (node (ref "IC12") (pin "N2") (pinfunction "DPCLK0,_DIFFOUT_L24n_N2") (pintype "bidirectional"))
    )
    (net (code "103") (name "/LMS_ENABLE_IQSEL1") (class "Default")
      (node (ref "IC12") (pin "N7") (pinfunction "DIFFOUT_B6n_N7") (pintype "bidirectional"))
    )
    (net (code "104") (name "/LMS_ENABLE_IQSEL2") (class "Default")
      (node (ref "IC12") (pin "N3") (pinfunction "DPCLK1,_DIFFOUT_L24p_N3") (pintype "bidirectional"))
    )
    (net (code "105") (name "/LMS_FCLK1") (class "Default")
      (node (ref "IC12") (pin "L3") (pinfunction "PLL_L_CLKOUTp,_DIFFOUT_L31p_L3") (pintype "bidirectional"))
    )
    (net (code "106") (name "/LMS_FCLK2") (class "Default")
      (node (ref "IC12") (pin "M3") (pinfunction "PLL_L_CLKOUTn,_DIFFOUT_L31n_M3") (pintype "bidirectional"))
    )
    (net (code "107") (name "/LMS_MCLK1") (class "Default")
      (node (ref "IC12") (pin "G5") (pinfunction "CLK0n,_DIFFOUT_L20n_G5") (pintype "bidirectional"))
    )
    (net (code "108") (name "/LMS_MCLK2") (class "Default")
      (node (ref "IC12") (pin "H4") (pinfunction "CLK1p,_DIFFOUT_L22p_H4") (pintype "bidirectional"))
    )
    (net (code "109") (name "/LMS_TXNRX1") (class "Default")
      (node (ref "IC12") (pin "N6") (pinfunction "DIFFOUT_B5n_N6") (pintype "bidirectional"))
    )
    (net (code "110") (name "/LMS_TXNRX2") (class "Default")
      (node (ref "IC12") (pin "C4") (pinfunction "nSTATUS,_DIFFOUT_T36p_C4") (pintype "bidirectional"))
      (node (ref "R41") (pin "2") (pinfunction "2_2") (pintype "passive"))
    )
    (net (code "111") (name "/RAPI_EMMC_EN") (class "Default")
      (node (ref "IC12") (pin "E1") (pinfunction "DIFFOUT_L7p_E1") (pintype "bidirectional"))
    )
    (net (code "112") (name "/RAPI_GPCLK1") (class "Default")
      (node (ref "IC12") (pin "H5") (pinfunction "CLK1n,_DIFFOUT_L22n_H5") (pintype "bidirectional"))
    )
    (net (code "113") (name "/RAPI_GPIO12") (class "Default")
      (node (ref "IC12") (pin "F10") (pinfunction "DPCLK2,_DIFFOUT_R30n_F10") (pintype "bidirectional"))
    )
    (net (code "114") (name "/RAPI_SPI0_CE0") (class "Default")
      (node (ref "IC12") (pin "E13") (pinfunction "CLK3n,_DIFFOUT_R20n_E13") (pintype "bidirectional"))
    )
    (net (code "115") (name "/RAPI_SPI0_MISO") (class "Default")
      (node (ref "IC12") (pin "K8") (pinfunction "CLK7p,_DIFFOUT_B20p_K8") (pintype "bidirectional"))
    )
    (net (code "116") (name "/RAPI_SPI0_MOSI") (class "Default")
      (node (ref "IC12") (pin "M11") (pinfunction "CLK6n,_DIFFOUT_B18n_M11") (pintype "bidirectional"))
    )
    (net (code "117") (name "/RAPI_SPI0_SCLK") (class "Default")
      (node (ref "IC12") (pin "F13") (pinfunction "CLK3p,_DIFFOUT_R20p_F13") (pintype "bidirectional"))
    )
    (net (code "118") (name "/RAPI_SPI1_CE0") (class "Default")
      (node (ref "IC12") (pin "A10") (pinfunction "DIFFOUT_T29p_A10") (pintype "bidirectional"))
    )
    (net (code "119") (name "/RAPI_SPI1_MISO") (class "Default")
      (node (ref "IC12") (pin "L11") (pinfunction "CLK6p,_DIFFOUT_B18p_L11") (pintype "bidirectional"))
    )
    (net (code "120") (name "/RAPI_SPI1_MOSI") (class "Default")
      (node (ref "IC12") (pin "K13") (pinfunction "I/O_K13") (pintype "bidirectional"))
    )
    (net (code "121") (name "/RAPI_SPI1_SCLK") (class "Default")
      (node (ref "IC12") (pin "G10") (pinfunction "CLK2n,_DIFFOUT_R18n_G10") (pintype "bidirectional"))
    )
    (net (code "122") (name "/SR_DIN") (class "Default")
      (node (ref "IC12") (pin "B7") (pinfunction "VREFB8N0_B7") (pintype "bidirectional"))
    )
    (net (code "123") (name "/SR_LATCH") (class "Default")
      (node (ref "IC12") (pin "D6") (pinfunction "CRC_ERROR,_DIFFOUT_T34n_D6") (pintype "bidirectional"))
    )
    (net (code "124") (name "/SR_SCLK") (class "Default")
      (node (ref "IC12") (pin "B9") (pinfunction "DEV_CLRn,_DIFFOUT_T28n_B9") (pintype "bidirectional"))
      (node (ref "R38") (pin "2") (pinfunction "2_2") (pintype "passive"))
    )
    (net (code "125") (name "/WIFI_PIO5") (class "Default")
      (node (ref "IC12") (pin "C9") (pinfunction "CLK5n,_DIFFOUT_T26n_C9") (pintype "bidirectional"))
    )
    (net (code "126") (name "GND") (class "Default")
      (node (ref "C100") (pin "2") (pinfunction "2_2") (pintype "passive"))
      (node (ref "C101") (pin "2") (pinfunction "2_2") (pintype "passive"))
      (node (ref "C102") (pin "2") (pinfunction "2_2") (pintype "passive"))
      (node (ref "C103") (pin "2") (pinfunction "2_2") (pintype "passive"))
      (node (ref "C104") (pin "2") (pinfunction "2_2") (pintype "passive"))
      (node (ref "C105") (pin "2") (pinfunction "2_2") (pintype "passive"))
      (node (ref "C106") (pin "1") (pinfunction "1_1") (pintype "passive"))
      (node (ref "C107") (pin "2") (pinfunction "2_2") (pintype "passive"))
      (node (ref "C108") (pin "2") (pinfunction "2_2") (pintype "passive"))
      (node (ref "C109") (pin "2") (pinfunction "2_2") (pintype "passive"))
      (node (ref "C110") (pin "2") (pinfunction "2_2") (pintype "passive"))
      (node (ref "C111") (pin "2") (pinfunction "2_2") (pintype "passive"))
      (node (ref "C112") (pin "2") (pinfunction "2_2") (pintype "passive"))
      (node (ref "C113") (pin "1") (pinfunction "1_1") (pintype "passive"))
      (node (ref "C114") (pin "2") (pinfunction "2_2") (pintype "passive"))
      (node (ref "C115") (pin "2") (pinfunction "2_2") (pintype "passive"))
      (node (ref "C116") (pin "2") (pinfunction "2_2") (pintype "passive"))
      (node (ref "C117") (pin "2") (pinfunction "2_2") (pintype "passive"))
      (node (ref "C118") (pin "2") (pinfunction "2_2") (pintype "passive"))
      (node (ref "C119") (pin "1") (pinfunction "1_1") (pintype "passive"))
      (node (ref "C120") (pin "2") (pinfunction "2_2") (pintype "passive"))
      (node (ref "C121") (pin "2") (pinfunction "2_2") (pintype "passive"))
      (node (ref "C122") (pin "2") (pinfunction "2_2") (pintype "passive"))
      (node (ref "C123") (pin "1") (pinfunction "1_1") (pintype "passive"))
      (node (ref "C124") (pin "2") (pinfunction "2_2") (pintype "passive"))
      (node (ref "C125") (pin "2") (pinfunction "2_2") (pintype "passive"))
      (node (ref "C126") (pin "2") (pinfunction "2_2") (pintype "passive"))
      (node (ref "C127") (pin "2") (pinfunction "2_2") (pintype "passive"))
      (node (ref "C128") (pin "2") (pinfunction "2_2") (pintype "passive"))
      (node (ref "C129") (pin "2") (pinfunction "2_2") (pintype "passive"))
      (node (ref "C130") (pin "2") (pinfunction "2_2") (pintype "passive"))
      (node (ref "C131") (pin "2") (pinfunction "2_2") (pintype "passive"))
      (node (ref "C98") (pin "1") (pinfunction "1_1") (pintype "passive"))
      (node (ref "C99") (pin "1") (pinfunction "1_1") (pintype "passive"))
      (node (ref "IC12") (pin "A1") (pinfunction "GND_A1") (pintype "passive"))
      (node (ref "IC12") (pin "A13") (pinfunction "GND_A13") (pintype "passive"))
      (node (ref "IC12") (pin "B8") (pinfunction "GND_B8") (pintype "passive"))
      (node (ref "IC12") (pin "C3") (pinfunction "GND_C3") (pintype "passive"))
      (node (ref "IC12") (pin "D2") (pinfunction "ANAIN1_D2") (pintype "passive"))
      (node (ref "IC12") (pin "D5") (pinfunction "GND_D5") (pintype "passive"))
      (node (ref "IC12") (pin "E11") (pinfunction "GND_E11") (pintype "passive"))
      (node (ref "IC12") (pin "E2") (pinfunction "REFGND_E2") (pintype "passive"))
      (node (ref "IC12") (pin "F3") (pinfunction "GND_F3") (pintype "passive"))
      (node (ref "IC12") (pin "F4") (pinfunction "DIFFOUT_L14n_F4") (pintype "bidirectional"))
      (node (ref "IC12") (pin "G7") (pinfunction "GND_G7") (pintype "passive"))
      (node (ref "IC12") (pin "H12") (pinfunction "GND_H12") (pintype "passive"))
      (node (ref "IC12") (pin "J4") (pinfunction "GND_J4") (pintype "passive"))
      (node (ref "IC12") (pin "L9") (pinfunction "GND_L9") (pintype "passive"))
      (node (ref "IC12") (pin "M6") (pinfunction "GND_M6") (pintype "passive"))
      (node (ref "IC12") (pin "N1") (pinfunction "GND_N1") (pintype "passive"))
      (node (ref "IC12") (pin "N13") (pinfunction "GND_N13") (pintype "passive"))
      (node (ref "J3") (pin "1") (pinfunction "1_1") (pintype "passive"))
      (node (ref "J4") (pin "10") (pinfunction "10_10") (pintype "passive"))
      (node (ref "J4") (pin "2") (pinfunction "2_2") (pintype "passive"))
      (node (ref "J5") (pin "9") (pinfunction "9_9") (pintype "passive"))
      (node (ref "R30") (pin "1") (pinfunction "1_1") (pintype "passive"))
      (node (ref "R31") (pin "2") (pinfunction "2_2") (pintype "passive"))
      (node (ref "R34") (pin "1") (pinfunction "1_1") (pintype "passive"))
      (node (ref "R35") (pin "1") (pinfunction "1_1") (pintype "passive"))
      (node (ref "R36") (pin "1") (pinfunction "1_1") (pintype "passive"))
      (node (ref "R37") (pin "1") (pinfunction "1_1") (pintype "passive"))
    )
    (net (code "127") (name "Net-(C98-Pad2)") (class "Default")
      (node (ref "C98") (pin "2") (pinfunction "2_2") (pintype "passive"))
      (node (ref "J5") (pin "10") (pinfunction "10_10") (pintype "passive"))
      (node (ref "R32") (pin "2") (pinfunction "2_2") (pintype "passive"))
      (node (ref "R33") (pin "2") (pinfunction "2_2") (pintype "passive"))
    )
    (net (code "128") (name "Net-(IC12A-JTAGEN)") (class "Default")
      (node (ref "IC12") (pin "E5") (pinfunction "JTAGEN_E5") (pintype "bidirectional"))
      (node (ref "R29") (pin "2") (pinfunction "2_2") (pintype "passive"))
    )
    (net (code "129") (name "Net-(IC12F-nCONFIG)") (class "Default")
      (node (ref "IC12") (pin "E7") (pinfunction "nCONFIG_E7") (pintype "input"))
      (node (ref "R40") (pin "2") (pinfunction "2_2") (pintype "passive"))
    )
    (net (code "130") (name "VCC1P8") (class "Default")
      (node (ref "C119") (pin "2") (pinfunction "2_2") (pintype "passive"))
      (node (ref "C120") (pin "1") (pinfunction "1_1") (pintype "passive"))
      (node (ref "C121") (pin "1") (pinfunction "1_1") (pintype "passive"))
      (node (ref "C122") (pin "1") (pinfunction "1_1") (pintype "passive"))
      (node (ref "IC12") (pin "F2") (pinfunction "VCCIO1A_F2") (pintype "passive"))
      (node (ref "IC12") (pin "G3") (pinfunction "VCCIO1B_G3") (pintype "passive"))
      (node (ref "J3") (pin "6") (pinfunction "6_6") (pintype "passive"))
      (node (ref "J4") (pin "4") (pinfunction "4_4") (pintype "passive"))
      (node (ref "R26") (pin "2") (pinfunction "2_2") (pintype "passive"))
      (node (ref "R28") (pin "2") (pinfunction "2_2") (pintype "passive"))
      (node (ref "R29") (pin "1") (pinfunction "1_1") (pintype "passive"))
    )
    (net (code "131") (name "VCC3P3") (class "Default")
      (node (ref "C100") (pin "1") (pinfunction "1_1") (pintype "passive"))
      (node (ref "C101") (pin "1") (pinfunction "1_1") (pintype "passive"))
      (node (ref "C102") (pin "1") (pinfunction "1_1") (pintype "passive"))
      (node (ref "C103") (pin "1") (pinfunction "1_1") (pintype "passive"))
      (node (ref "C104") (pin "1") (pinfunction "1_1") (pintype "passive"))
      (node (ref "C105") (pin "1") (pinfunction "1_1") (pintype "passive"))
      (node (ref "C113") (pin "2") (pinfunction "2_2") (pintype "passive"))
      (node (ref "C114") (pin "1") (pinfunction "1_1") (pintype "passive"))
      (node (ref "C115") (pin "1") (pinfunction "1_1") (pintype "passive"))
      (node (ref "C116") (pin "1") (pinfunction "1_1") (pintype "passive"))
      (node (ref "C117") (pin "1") (pinfunction "1_1") (pintype "passive"))
      (node (ref "C118") (pin "1") (pinfunction "1_1") (pintype "passive"))
      (node (ref "C123") (pin "2") (pinfunction "2_2") (pintype "passive"))
      (node (ref "C124") (pin "1") (pinfunction "1_1") (pintype "passive"))
      (node (ref "C125") (pin "1") (pinfunction "1_1") (pintype "passive"))
      (node (ref "C126") (pin "1") (pinfunction "1_1") (pintype "passive"))
      (node (ref "C127") (pin "1") (pinfunction "1_1") (pintype "passive"))
      (node (ref "C128") (pin "1") (pinfunction "1_1") (pintype "passive"))
      (node (ref "C129") (pin "1") (pinfunction "1_1") (pintype "passive"))
      (node (ref "C130") (pin "1") (pinfunction "1_1") (pintype "passive"))
      (node (ref "C131") (pin "1") (pinfunction "1_1") (pintype "passive"))
      (node (ref "C99") (pin "2") (pinfunction "2_2") (pintype "passive"))
      (node (ref "FR35") (pin "1") (pinfunction "1_1") (pintype "passive"))
      (node (ref "IC12") (pin "C6") (pinfunction "VCCIO8_C6") (pintype "passive"))
      (node (ref "IC12") (pin "C7") (pinfunction "VCCIO8_C7") (pintype "passive"))
      (node (ref "IC12") (pin "C8") (pinfunction "VCCIO8_C8") (pintype "passive"))
      (node (ref "IC12") (pin "F11") (pinfunction "VCCIO6_F11") (pintype "passive"))
      (node (ref "IC12") (pin "F7") (pinfunction "VCC_ONE_F7") (pintype "passive"))
      (node (ref "IC12") (pin "G11") (pinfunction "VCCIO6_G11") (pintype "passive"))
      (node (ref "IC12") (pin "G6") (pinfunction "VCC_ONE_G6") (pintype "passive"))
      (node (ref "IC12") (pin "G8") (pinfunction "VCC_ONE_G8") (pintype "passive"))
      (node (ref "IC12") (pin "H11") (pinfunction "VCCIO5_H11") (pintype "passive"))
      (node (ref "IC12") (pin "H7") (pinfunction "VCC_ONE_H7") (pintype "passive"))
      (node (ref "IC12") (pin "J11") (pinfunction "VCCIO5_J11") (pintype "passive"))
      (node (ref "IC12") (pin "J3") (pinfunction "VCCIO2_J3") (pintype "passive"))
      (node (ref "IC12") (pin "K3") (pinfunction "VCCIO2_K3") (pintype "passive"))
      (node (ref "IC12") (pin "L6") (pinfunction "VCCIO3_L6") (pintype "passive"))
      (node (ref "IC12") (pin "L7") (pinfunction "VCCIO3_L7") (pintype "passive"))
      (node (ref "IC12") (pin "L8") (pinfunction "VCCIO3_L8") (pintype "passive"))
      (node (ref "R27") (pin "1") (pinfunction "1_1") (pintype "passive"))
      (node (ref "R32") (pin "1") (pinfunction "1_1") (pintype "passive"))
      (node (ref "R38") (pin "1") (pinfunction "1_1") (pintype "passive"))
      (node (ref "R39") (pin "1") (pinfunction "1_1") (pintype "passive"))
      (node (ref "R40") (pin "1") (pinfunction "1_1") (pintype "passive"))
      (node (ref "R41") (pin "1") (pinfunction "1_1") (pintype "passive"))
      (node (ref "R42") (pin "1") (pinfunction "1_1") (pintype "passive"))
    )
    (net (code "132") (name "VCC3P3A") (class "Default")
      (node (ref "C106") (pin "2") (pinfunction "2_2") (pintype "passive"))
      (node (ref "C107") (pin "1") (pinfunction "1_1") (pintype "passive"))
      (node (ref "C108") (pin "1") (pinfunction "1_1") (pintype "passive"))
      (node (ref "C109") (pin "1") (pinfunction "1_1") (pintype "passive"))
      (node (ref "C110") (pin "1") (pinfunction "1_1") (pintype "passive"))
      (node (ref "C111") (pin "1") (pinfunction "1_1") (pintype "passive"))
      (node (ref "C112") (pin "1") (pinfunction "1_1") (pintype "passive"))
      (node (ref "FR35") (pin "2") (pinfunction "2_2") (pintype "passive"))
      (node (ref "IC12") (pin "D10") (pinfunction "VCCA2_D10") (pintype "passive"))
      (node (ref "IC12") (pin "D3") (pinfunction "ADC_VREF_D3") (pintype "passive"))
      (node (ref "IC12") (pin "D4") (pinfunction "VCCA3_D4") (pintype "passive"))
      (node (ref "IC12") (pin "K4") (pinfunction "VCCA1_K4") (pintype "passive"))
      (node (ref "IC12") (pin "K9") (pinfunction "VCCA4_K9") (pintype "passive"))
    )
    (net (code "133") (name "VCC5P0") (class "Default")
      (node (ref "J3") (pin "7") (pinfunction "7_7") (pintype "passive"))
      (node (ref "R33") (pin "1") (pinfunction "1_1") (pintype "passive"))
    )
    (net (code "134") (name "unconnected-(IC12A-DIFFOUT_L3n-PadE3)") (class "Default")
      (node (ref "IC12") (pin "E3") (pinfunction "DIFFOUT_L3n_E3") (pintype "bidirectional+no_connect"))
    )
    (net (code "135") (name "unconnected-(IC12A-DIFFOUT_L3p-PadE4)") (class "Default")
      (node (ref "IC12") (pin "E4") (pinfunction "DIFFOUT_L3p_E4") (pintype "bidirectional+no_connect"))
    )
    (net (code "136") (name "unconnected-(J4-Pad6)") (class "Default")
      (node (ref "J4") (pin "6") (pinfunction "6_6") (pintype "passive+no_connect"))
    )
    (net (code "137") (name "unconnected-(J4-Pad7)") (class "Default")
      (node (ref "J4") (pin "7") (pinfunction "7_7") (pintype "passive+no_connect"))
    )
    (net (code "138") (name "unconnected-(J4-Pad8)") (class "Default")
      (node (ref "J4") (pin "8") (pinfunction "8_8") (pintype "passive+no_connect"))
    )
  )
)
